# LCD_Display.net
KiCad netlist of a schematic drawn in Altium Designer
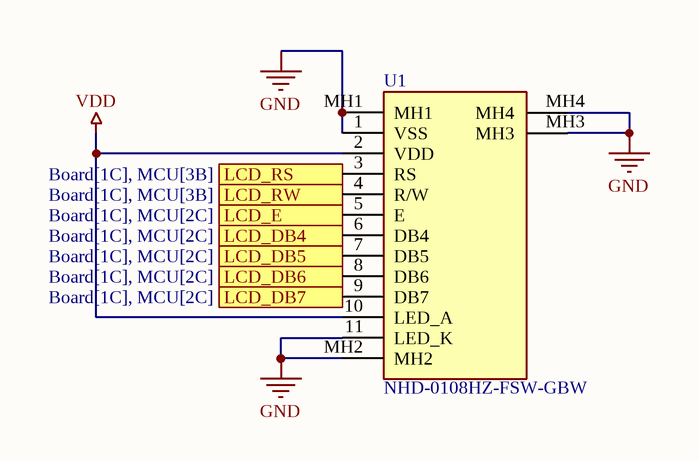
[diagram p0: LCD_Display.SchDoc]

(export (version "E")
  (design (tool "Eeschema 10.0.6"))
  (components
    (comp (ref "U1")
      (value "NHD-0108HZ-FSW-GBW")
      (footprint "SamacSys:NHD0108HZFSWGBW")
      (description "Display")
      (fields (field (name "MOUSER PART NUMBER") "763-0108HZ-FSW-GBW"))
      (libsource (lib "schematics") (part "NHD-0108HZ-FSW-GBW"))
    )
  )
  (nets
    (net (code "1") (name "/LCD_DB4") (class "Default")
      (node (ref "U1") (pin "6") (pinfunction "DB4_6") (pintype "passive"))
    )
    (net (code "2") (name "/LCD_DB5") (class "Default")
      (node (ref "U1") (pin "7") (pinfunction "DB5_7") (pintype "passive"))
    )
    (net (code "3") (name "/LCD_DB6") (class "Default")
      (node (ref "U1") (pin "8") (pinfunction "DB6_8") (pintype "passive"))
    )
    (net (code "4") (name "/LCD_DB7") (class "Default")
      (node (ref "U1") (pin "9") (pinfunction "DB7_9") (pintype "passive"))
    )
    (net (code "5") (name "/LCD_E") (class "Default")
      (node (ref "U1") (pin "5") (pinfunction "E_5") (pintype "passive"))
    )
    (net (code "6") (name "/LCD_RS") (class "Default")
      (node (ref "U1") (pin "3") (pinfunction "RS_3") (pintype "passive"))
    )
    (net (code "7") (name "/LCD_RW") (class "Default")
      (node (ref "U1") (pin "4") (pinfunction "R/W_4") (pintype "passive"))
    )
    (net (code "8") (name "GND") (class "Default")
      (node (ref "U1") (pin "1") (pinfunction "VSS_1") (pintype "passive"))
      (node (ref "U1") (pin "11") (pinfunction "LED_K_11") (pintype "passive"))
      (node (ref "U1") (pin "MH1") (pinfunction "MH1_MH1") (pintype "passive"))
      (node (ref "U1") (pin "MH2") (pinfunction "MH2_MH2") (pintype "passive"))
      (node (ref "U1") (pin "MH3") (pinfunction "MH3_MH3") (pintype "passive"))
      (node (ref "U1") (pin "MH4") (pinfunction "MH4_MH4") (pintype "passive"))
    )
    (net (code "9") (name "VDD") (class "Default")
      (node (ref "U1") (pin "10") (pinfunction "LED_A_10") (pintype "passive"))
      (node (ref "U1") (pin "2") (pinfunction "VDD_2") (pintype "passive"))
    )
  )
)
